# cc2652p_ch340e.net
KiCad netlist of a schematic drawn in EAGLE
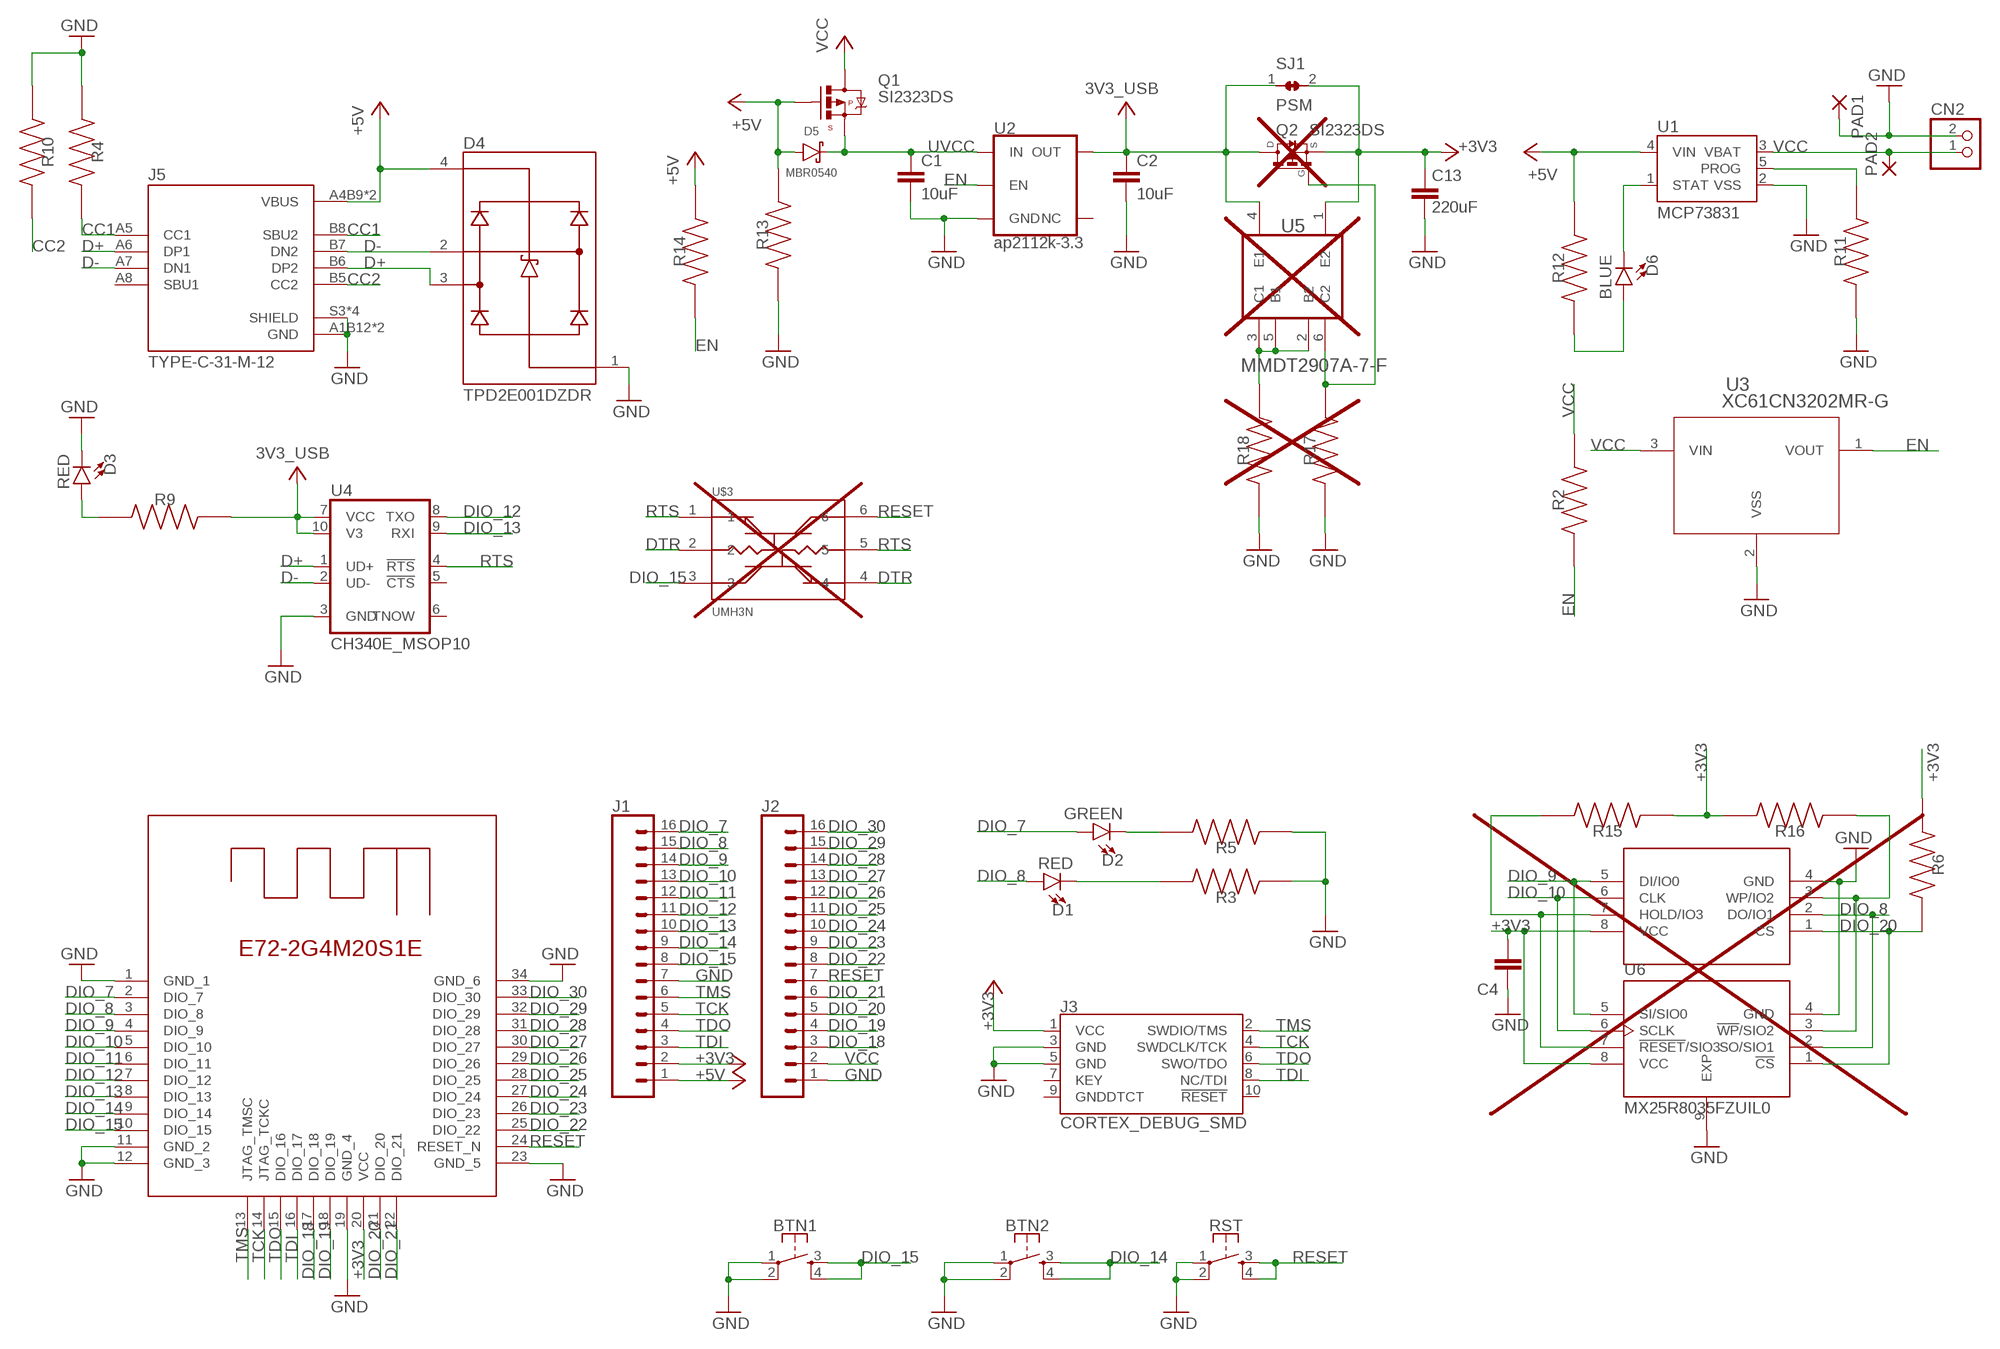
[diagram p0: schematic, sheet 1]

(export (version "E")
  (design (tool "Eeschema 10.0.6"))
  (components
    (comp (ref "BTN1")
      (value "MOMENTARY-SWITCH-SPST-2-SMD-4.6X2.8MM")
      (footprint "eagle-import:TACTILE_SWITCH_SMD_4.6X2.8MM")
      (libsource (lib "eagle-import") (part "MOMENTARY-SWITCH-SPST-2-SMD-4.6X2.8MM"))
    )
    (comp (ref "BTN2")
      (value "MOMENTARY-SWITCH-SPST-2-SMD-4.6X2.8MM")
      (footprint "eagle-import:TACTILE_SWITCH_SMD_4.6X2.8MM")
      (libsource (lib "eagle-import") (part "MOMENTARY-SWITCH-SPST-2-SMD-4.6X2.8MM"))
    )
    (comp (ref "C1")
      (value "10uF")
      (footprint "eagle-import:0603")
      (libsource (lib "eagle-import") (part "10UF-0603-6.3V-20%"))
    )
    (comp (ref "C2")
      (value "10uF")
      (footprint "eagle-import:0603")
      (libsource (lib "eagle-import") (part "10UF-0603-6.3V-20%"))
    )
    (comp (ref "C4")
      (value "100n")
      (footprint "eagle-import:CAPC1005X40N")
      (fields (field (name "MF") "Yageo") (field (name "MP") "RC0402FR-073M6L"))
      (libsource (lib "eagle-import") (part "CAP0402"))
    )
    (comp (ref "C13")
      (value "220uF")
      (footprint "eagle-import:CAPM7343X310")
      (libsource (lib "eagle-import") (part "CTANTALUM-2917(7343-METRIC)_"))
    )
    (comp (ref "CN2")
      (value "JST_2PIN-SMT-RA")
      (footprint "eagle-import:JST-PH-2-SMT-RA")
      (libsource (lib "eagle-import") (part "JST_2PIN-SMT-RA"))
    )
    (comp (ref "D1")
      (value "RED")
      (footprint "eagle-import:LED-0603")
      (libsource (lib "eagle-import") (part "LED-RED0603"))
    )
    (comp (ref "D2")
      (value "GREEN")
      (footprint "eagle-import:LED-0603")
      (libsource (lib "eagle-import") (part "LED-GREEN0603"))
    )
    (comp (ref "D3")
      (value "RED")
      (footprint "eagle-import:LED-0603")
      (libsource (lib "eagle-import") (part "LED-RED0603"))
    )
    (comp (ref "D4")
      (value "TPD2E001DZDR")
      (footprint "eagle-import:SOT192P237X122-4N")
      (fields (field (name "MF") "Texas Instruments"))
      (libsource (lib "eagle-import") (part "TPD2E001DZDR"))
    )
    (comp (ref "D5")
      (value "MBR0540")
      (footprint "eagle-import:SOD-323")
      (libsource (lib "eagle-import") (part "DIODE-SCHOTTKY"))
    )
    (comp (ref "D6")
      (value "BLUE")
      (footprint "eagle-import:LED-0603")
      (libsource (lib "eagle-import") (part "LED-BLUE0603"))
    )
    (comp (ref "J1")
      (value "CONN_161X16_NO_SILK")
      (footprint "eagle-import:1X16_NO_SILK")
      (libsource (lib "eagle-import") (part "CONN_161X16_NO_SILK"))
    )
    (comp (ref "J2")
      (value "CONN_161X16_NO_SILK")
      (footprint "eagle-import:1X16_NO_SILK")
      (libsource (lib "eagle-import") (part "CONN_161X16_NO_SILK"))
    )
    (comp (ref "J3")
      (value "CORTEX_DEBUG_SMD")
      (footprint "eagle-import:SAMTECH_FTSH-105-01")
      (libsource (lib "eagle-import") (part "CORTEX_DEBUG_SMD"))
    )
    (comp (ref "J5")
      (value "TYPE-C-31-M-12")
      (footprint "eagle-import:HRO_TYPE-C-31-M-12")
      (fields (field (name "MF") "HRO Electronics Co., Ltd."))
      (libsource (lib "eagle-import") (part "TYPE-C-31-M-12"))
    )
    (comp (ref "PAD1")
      (value "WIREPADSMD1,27-254")
      (footprint "eagle-import:SMD1,27-2,54")
      (libsource (lib "eagle-import") (part "WIREPADSMD1,27-254"))
    )
    (comp (ref "PAD2")
      (value "WIREPADSMD1,27-254")
      (footprint "eagle-import:SMD1,27-2,54")
      (libsource (lib "eagle-import") (part "WIREPADSMD1,27-254"))
    )
    (comp (ref "Q1")
      (value "SI2323DS")
      (footprint "eagle-import:SOT23")
      (libsource (lib "eagle-import") (part "MOSFET-PCHANNEL"))
    )
    (comp (ref "Q2")
      (value "SI2323DS")
      (footprint "eagle-import:SOT23")
      (fields (field (name "MF") "Vishay Siliconix"))
      (libsource (lib "eagle-import") (part "SI2323DS"))
    )
    (comp (ref "R2")
      (value "10k")
      (footprint "eagle-import:RESC1005X40N")
      (fields (field (name "MF") "Yageo") (field (name "MP") "RC0402FR-073M6L"))
      (libsource (lib "eagle-import") (part "RC0402FR-073M6L"))
    )
    (comp (ref "R3")
      (value "2.2k")
      (footprint "eagle-import:RESC1005X40N")
      (fields (field (name "MF") "Yageo") (field (name "MP") "RC0402FR-073M6L"))
      (libsource (lib "eagle-import") (part "RC0402FR-073M6L"))
    )
    (comp (ref "R4")
      (value "5.1k")
      (footprint "eagle-import:RESC1005X40N")
      (fields (field (name "MF") "Yageo") (field (name "MP") "RC0402FR-073M6L"))
      (libsource (lib "eagle-import") (part "RC0402FR-073M6L"))
    )
    (comp (ref "R5")
      (value "2.2k")
      (footprint "eagle-import:RESC1005X40N")
      (fields (field (name "MF") "Yageo") (field (name "MP") "RC0402FR-073M6L"))
      (libsource (lib "eagle-import") (part "RC0402FR-073M6L"))
    )
    (comp (ref "R6")
      (value "2.2k")
      (footprint "eagle-import:RESC1005X40N")
      (fields (field (name "MF") "Yageo") (field (name "MP") "RC0402FR-073M6L"))
      (libsource (lib "eagle-import") (part "RC0402FR-073M6L"))
    )
    (comp (ref "R9")
      (value "2.2k")
      (footprint "eagle-import:RESC1005X40N")
      (fields (field (name "MF") "Yageo") (field (name "MP") "RC0402FR-073M6L"))
      (libsource (lib "eagle-import") (part "RC0402FR-073M6L"))
    )
    (comp (ref "R10")
      (value "5.1k")
      (footprint "eagle-import:RESC1005X40N")
      (fields (field (name "MF") "Yageo") (field (name "MP") "RC0402FR-073M6L"))
      (libsource (lib "eagle-import") (part "RC0402FR-073M6L"))
    )
    (comp (ref "R11")
      (value "2k")
      (footprint "eagle-import:RESC1005X40N")
      (fields (field (name "MF") "Yageo") (field (name "MP") "RC0402FR-073M6L"))
      (libsource (lib "eagle-import") (part "RC0402FR-073M6L"))
    )
    (comp (ref "R12")
      (value "2.2k")
      (footprint "eagle-import:RESC1005X40N")
      (fields (field (name "MF") "Yageo") (field (name "MP") "RC0402FR-073M6L"))
      (libsource (lib "eagle-import") (part "RC0402FR-073M6L"))
    )
    (comp (ref "R13")
      (value "10k")
      (footprint "eagle-import:RESC1005X40N")
      (fields (field (name "MF") "Yageo") (field (name "MP") "RC0402FR-073M6L"))
      (libsource (lib "eagle-import") (part "RC0402FR-073M6L"))
    )
    (comp (ref "R14")
      (value "10k")
      (footprint "eagle-import:RESC1005X40N")
      (fields (field (name "MF") "Yageo") (field (name "MP") "RC0402FR-073M6L"))
      (libsource (lib "eagle-import") (part "RC0402FR-073M6L"))
    )
    (comp (ref "R15")
      (value "0")
      (footprint "eagle-import:RESC1005X40N")
      (fields (field (name "MF") "Yageo") (field (name "MP") "RC0402FR-073M6L"))
      (libsource (lib "eagle-import") (part "RC0402FR-073M6L"))
    )
    (comp (ref "R16")
      (value "0")
      (footprint "eagle-import:RESC1005X40N")
      (fields (field (name "MF") "Yageo") (field (name "MP") "RC0402FR-073M6L"))
      (libsource (lib "eagle-import") (part "RC0402FR-073M6L"))
    )
    (comp (ref "R17")
      (value "100k")
      (footprint "eagle-import:RESC1005X40N")
      (fields (field (name "MF") "Yageo") (field (name "MP") "RC0402FR-073M6L"))
      (libsource (lib "eagle-import") (part "RC0402FR-073M6L"))
    )
    (comp (ref "R18")
      (value "100k")
      (footprint "eagle-import:RESC1005X40N")
      (fields (field (name "MF") "Yageo") (field (name "MP") "RC0402FR-073M6L"))
      (libsource (lib "eagle-import") (part "RC0402FR-073M6L"))
    )
    (comp (ref "RST")
      (value "MOMENTARY-SWITCH-SPST-2-SMD-4.6X2.8MM")
      (footprint "eagle-import:TACTILE_SWITCH_SMD_4.6X2.8MM")
      (libsource (lib "eagle-import") (part "MOMENTARY-SWITCH-SPST-2-SMD-4.6X2.8MM"))
    )
    (comp (ref "SJ1")
      (value "PSM")
      (footprint "eagle-import:SMALL_SOLDER_JUMPER_CLOSED")
      (libsource (lib "eagle-import") (part "SMALL_SOLDER_JUMPER_CLOSED"))
    )
    (comp (ref "U$1")
      (value "E72-2G4M20S1E")
      (footprint "eagle-import:E72-2G4M20S1E")
      (libsource (lib "eagle-import") (part "E72-2G4M20S1E"))
    )
    (comp (ref "U$2")
      (value "MX25R8035FM1IL0")
      (footprint "eagle-import:SO-8")
      (fields (field (name "MF") "Winbond Electronics") (field (name "MP") "W25Q80BVSNIG"))
      (libsource (lib "eagle-import") (part "W25Q80BVSNIG"))
    )
    (comp (ref "U$3")
      (value "UMH3N")
      (footprint "eagle-import:SOP65P210X100-6N")
      (fields (field (name "MF") "Rohm"))
      (libsource (lib "eagle-import") (part "UMH3N"))
    )
    (comp (ref "U1")
      (value "MCP73831")
      (footprint "eagle-import:SOT23-5")
      (libsource (lib "eagle-import") (part "MCP73831"))
    )
    (comp (ref "U2")
      (value "ap2112k-3.3")
      (footprint "eagle-import:SOT23-5")
      (libsource (lib "eagle-import") (part "V_REG_AP2112K-3.3V"))
    )
    (comp (ref "U3")
      (value "XC61CN3202MR-G")
      (footprint "eagle-import:XC61C_SOT-23_TOR")
      (libsource (lib "eagle-import") (part "XC61CN3202MR-G"))
    )
    (comp (ref "U4")
      (value "CH340E_MSOP10")
      (footprint "eagle-import:MSOP10")
      (fields (field (name "MF") "WCH") (field (name "MP") "CH340E"))
      (libsource (lib "eagle-import") (part "CH340E_MSOP10"))
    )
    (comp (ref "U5")
      (value "MMDT2907A-7-F")
      (footprint "eagle-import:SOT65P210X110-6N")
      (fields (field (name "MF") "Diodes Inc."))
      (libsource (lib "eagle-import") (part "MMDT2907A-7-F"))
    )
    (comp (ref "U6")
      (value "MX25R8035FZUIL0")
      (footprint "eagle-import:PSON50P200X300X60-9N")
      (fields (field (name "MF") "Macronix"))
      (libsource (lib "eagle-import") (part "MX25R8035FZUIL0"))
    )
  )
  (nets
    (net (code "1") (name "+3V3") (class "Default")
      (node (ref "C13") (pin "1") (pinfunction "1_1") (pintype "passive"))
      (node (ref "C4") (pin "2") (pinfunction "2_2") (pintype "passive"))
      (node (ref "J1") (pin "2") (pinfunction "2_2") (pintype "passive"))
      (node (ref "J3") (pin "1") (pinfunction "VCC_1") (pintype "bidirectional"))
      (node (ref "Q2") (pin "2") (pinfunction "S_2") (pintype "passive"))
      (node (ref "R15") (pin "1") (pinfunction "1_1") (pintype "passive"))
      (node (ref "R16") (pin "2") (pinfunction "2_2") (pintype "passive"))
      (node (ref "R6") (pin "1") (pinfunction "1_1") (pintype "passive"))
      (node (ref "SJ1") (pin "2") (pinfunction "2_2") (pintype "bidirectional"))
      (node (ref "U$1") (pin "20") (pinfunction "VCC_20") (pintype "bidirectional"))
      (node (ref "U$2") (pin "8") (pinfunction "VCC_8") (pintype "bidirectional"))
      (node (ref "U5") (pin "1") (pinfunction "E2_1") (pintype "passive"))
      (node (ref "U6") (pin "8") (pinfunction "VCC_8") (pintype "power_in"))
    )
    (net (code "2") (name "+5V") (class "Default")
      (node (ref "D4") (pin "4") (pinfunction "VCC_4") (pintype "power_in"))
      (node (ref "D5") (pin "A") (pinfunction "A_A") (pintype "passive"))
      (node (ref "J1") (pin "1") (pinfunction "1_1") (pintype "passive"))
      (node (ref "J5") (pin "A4B9") (pinfunction "VBUS_A4B9") (pintype "power_in"))
      (node (ref "J5") (pin "B4A9") (pinfunction "VBUS_B4A9") (pintype "power_in"))
      (node (ref "Q1") (pin "1") (pinfunction "G_1") (pintype "passive"))
      (node (ref "R12") (pin "2") (pinfunction "2_2") (pintype "passive"))
      (node (ref "R13") (pin "2") (pinfunction "2_2") (pintype "passive"))
      (node (ref "R14") (pin "2") (pinfunction "2_2") (pintype "passive"))
      (node (ref "U1") (pin "4") (pinfunction "VIN_4") (pintype "power_in"))
    )
    (net (code "3") (name "/CC1") (class "Default")
      (node (ref "J5") (pin "A5") (pinfunction "CC1_A5") (pintype "bidirectional"))
      (node (ref "J5") (pin "B8") (pinfunction "SBU2_B8") (pintype "bidirectional"))
      (node (ref "R4") (pin "2") (pinfunction "2_2") (pintype "passive"))
    )
    (net (code "4") (name "/CC2") (class "Default")
      (node (ref "J5") (pin "B5") (pinfunction "CC2_B5") (pintype "bidirectional"))
      (node (ref "R10") (pin "2") (pinfunction "2_2") (pintype "passive"))
    )
    (net (code "5") (name "/D+") (class "Default")
      (node (ref "D4") (pin "3") (pinfunction "IO2_3") (pintype "bidirectional"))
      (node (ref "J5") (pin "A6") (pinfunction "DP1_A6") (pintype "bidirectional"))
      (node (ref "J5") (pin "B6") (pinfunction "DP2_B6") (pintype "bidirectional"))
      (node (ref "U4") (pin "1") (pinfunction "UD+_1") (pintype "bidirectional"))
    )
    (net (code "6") (name "/D-") (class "Default")
      (node (ref "D4") (pin "2") (pinfunction "IO1_2") (pintype "bidirectional"))
      (node (ref "J5") (pin "A7") (pinfunction "DN1_A7") (pintype "bidirectional"))
      (node (ref "J5") (pin "B7") (pinfunction "DN2_B7") (pintype "bidirectional"))
      (node (ref "U4") (pin "2") (pinfunction "UD-_2") (pintype "bidirectional"))
    )
    (net (code "7") (name "/DIO_7") (class "Default")
      (node (ref "D2") (pin "A") (pinfunction "A_A") (pintype "passive"))
      (node (ref "J1") (pin "16") (pinfunction "16_16") (pintype "passive"))
      (node (ref "U$1") (pin "2") (pinfunction "DIO_7_2") (pintype "bidirectional"))
    )
    (net (code "8") (name "/DIO_8") (class "Default")
      (node (ref "D1") (pin "A") (pinfunction "A_A") (pintype "passive"))
      (node (ref "J1") (pin "15") (pinfunction "15_15") (pintype "passive"))
      (node (ref "U$1") (pin "3") (pinfunction "DIO_8_3") (pintype "bidirectional"))
      (node (ref "U$2") (pin "2") (pinfunction "DO/IO1_2") (pintype "bidirectional"))
      (node (ref "U6") (pin "2") (pinfunction "SO/SIO1_2") (pintype "bidirectional"))
    )
    (net (code "9") (name "/DIO_9") (class "Default")
      (node (ref "J1") (pin "14") (pinfunction "14_14") (pintype "passive"))
      (node (ref "U$1") (pin "4") (pinfunction "DIO_9_4") (pintype "bidirectional"))
      (node (ref "U$2") (pin "5") (pinfunction "DI/IO0_5") (pintype "bidirectional"))
      (node (ref "U6") (pin "5") (pinfunction "SI/SIO0_5") (pintype "bidirectional"))
    )
    (net (code "10") (name "/DIO_10") (class "Default")
      (node (ref "J1") (pin "13") (pinfunction "13_13") (pintype "passive"))
      (node (ref "U$1") (pin "5") (pinfunction "DIO_10_5") (pintype "bidirectional"))
      (node (ref "U$2") (pin "6") (pinfunction "CLK_6") (pintype "bidirectional"))
      (node (ref "U6") (pin "6") (pinfunction "SCLK_6") (pintype "input"))
    )
    (net (code "11") (name "/DIO_11") (class "Default")
      (node (ref "J1") (pin "12") (pinfunction "12_12") (pintype "passive"))
      (node (ref "U$1") (pin "6") (pinfunction "DIO_11_6") (pintype "bidirectional"))
    )
    (net (code "12") (name "/DIO_12") (class "Default")
      (node (ref "J1") (pin "11") (pinfunction "11_11") (pintype "passive"))
      (node (ref "U$1") (pin "7") (pinfunction "DIO_12_7") (pintype "bidirectional"))
      (node (ref "U4") (pin "8") (pinfunction "TXO_8") (pintype "bidirectional"))
    )
    (net (code "13") (name "/DIO_13") (class "Default")
      (node (ref "J1") (pin "10") (pinfunction "10_10") (pintype "passive"))
      (node (ref "U$1") (pin "8") (pinfunction "DIO_13_8") (pintype "bidirectional"))
      (node (ref "U4") (pin "9") (pinfunction "RXI_9") (pintype "bidirectional"))
    )
    (net (code "14") (name "/DIO_14") (class "Default")
      (node (ref "BTN2") (pin "3") (pinfunction "3_3") (pintype "passive"))
      (node (ref "BTN2") (pin "4") (pinfunction "4_4") (pintype "passive"))
      (node (ref "J1") (pin "9") (pinfunction "9_9") (pintype "passive"))
      (node (ref "U$1") (pin "9") (pinfunction "DIO_14_9") (pintype "bidirectional"))
    )
    (net (code "15") (name "/DIO_15") (class "Default")
      (node (ref "BTN1") (pin "3") (pinfunction "3_3") (pintype "passive"))
      (node (ref "BTN1") (pin "4") (pinfunction "4_4") (pintype "passive"))
      (node (ref "J1") (pin "8") (pinfunction "8_8") (pintype "passive"))
      (node (ref "U$1") (pin "10") (pinfunction "DIO_15_10") (pintype "bidirectional"))
      (node (ref "U$3") (pin "3") (pinfunction "3_3") (pintype "bidirectional"))
    )
    (net (code "16") (name "/DIO_18") (class "Default")
      (node (ref "J2") (pin "3") (pinfunction "3_3") (pintype "passive"))
      (node (ref "U$1") (pin "17") (pinfunction "DIO_18_17") (pintype "bidirectional"))
    )
    (net (code "17") (name "/DIO_19") (class "Default")
      (node (ref "J2") (pin "4") (pinfunction "4_4") (pintype "passive"))
      (node (ref "U$1") (pin "18") (pinfunction "DIO_19_18") (pintype "bidirectional"))
    )
    (net (code "18") (name "/DIO_20") (class "Default")
      (node (ref "J2") (pin "5") (pinfunction "5_5") (pintype "passive"))
      (node (ref "R6") (pin "2") (pinfunction "2_2") (pintype "passive"))
      (node (ref "U$1") (pin "21") (pinfunction "DIO_20_21") (pintype "bidirectional"))
      (node (ref "U$2") (pin "1") (pinfunction "CS_1") (pintype "bidirectional"))
      (node (ref "U6") (pin "1") (pinfunction "~{CS}_1") (pintype "input"))
    )
    (net (code "19") (name "/DIO_21") (class "Default")
      (node (ref "J2") (pin "6") (pinfunction "6_6") (pintype "passive"))
      (node (ref "U$1") (pin "22") (pinfunction "DIO_21_22") (pintype "bidirectional"))
    )
    (net (code "20") (name "/DIO_22") (class "Default")
      (node (ref "J2") (pin "8") (pinfunction "8_8") (pintype "passive"))
      (node (ref "U$1") (pin "25") (pinfunction "DIO_22_25") (pintype "bidirectional"))
    )
    (net (code "21") (name "/DIO_23") (class "Default")
      (node (ref "J2") (pin "9") (pinfunction "9_9") (pintype "passive"))
      (node (ref "U$1") (pin "26") (pinfunction "DIO_23_26") (pintype "bidirectional"))
    )
    (net (code "22") (name "/DIO_24") (class "Default")
      (node (ref "J2") (pin "10") (pinfunction "10_10") (pintype "passive"))
      (node (ref "U$1") (pin "27") (pinfunction "DIO_24_27") (pintype "bidirectional"))
    )
    (net (code "23") (name "/DIO_25") (class "Default")
      (node (ref "J2") (pin "11") (pinfunction "11_11") (pintype "passive"))
      (node (ref "U$1") (pin "28") (pinfunction "DIO_25_28") (pintype "bidirectional"))
    )
    (net (code "24") (name "/DIO_26") (class "Default")
      (node (ref "J2") (pin "12") (pinfunction "12_12") (pintype "passive"))
      (node (ref "U$1") (pin "29") (pinfunction "DIO_26_29") (pintype "bidirectional"))
    )
    (net (code "25") (name "/DIO_27") (class "Default")
      (node (ref "J2") (pin "13") (pinfunction "13_13") (pintype "passive"))
      (node (ref "U$1") (pin "30") (pinfunction "DIO_27_30") (pintype "bidirectional"))
    )
    (net (code "26") (name "/DIO_28") (class "Default")
      (node (ref "J2") (pin "14") (pinfunction "14_14") (pintype "passive"))
      (node (ref "U$1") (pin "31") (pinfunction "DIO_28_31") (pintype "bidirectional"))
    )
    (net (code "27") (name "/DIO_29") (class "Default")
      (node (ref "J2") (pin "15") (pinfunction "15_15") (pintype "passive"))
      (node (ref "U$1") (pin "32") (pinfunction "DIO_29_32") (pintype "bidirectional"))
    )
    (net (code "28") (name "/DIO_30") (class "Default")
      (node (ref "J2") (pin "16") (pinfunction "16_16") (pintype "passive"))
      (node (ref "U$1") (pin "33") (pinfunction "DIO_30_33") (pintype "bidirectional"))
    )
    (net (code "29") (name "/DTR") (class "Default")
      (node (ref "U$3") (pin "2") (pinfunction "2_2") (pintype "bidirectional"))
      (node (ref "U$3") (pin "4") (pinfunction "4_4") (pintype "bidirectional"))
    )
    (net (code "30") (name "/EN") (class "Default")
      (node (ref "R14") (pin "1") (pinfunction "1_1") (pintype "passive"))
      (node (ref "R2") (pin "1") (pinfunction "1_1") (pintype "passive"))
      (node (ref "U2") (pin "3") (pinfunction "EN_3") (pintype "input"))
      (node (ref "U3") (pin "1") (pinfunction "VOUT_1") (pintype "output"))
    )
    (net (code "31") (name "/RESET") (class "Default")
      (node (ref "J2") (pin "7") (pinfunction "7_7") (pintype "passive"))
      (node (ref "RST") (pin "3") (pinfunction "3_3") (pintype "passive"))
      (node (ref "RST") (pin "4") (pinfunction "4_4") (pintype "passive"))
      (node (ref "U$1") (pin "24") (pinfunction "RESET_N_24") (pintype "bidirectional"))
      (node (ref "U$3") (pin "6") (pinfunction "6_6") (pintype "bidirectional"))
    )
    (net (code "32") (name "/RTS") (class "Default")
      (node (ref "U$3") (pin "1") (pinfunction "1_1") (pintype "bidirectional"))
      (node (ref "U$3") (pin "5") (pinfunction "5_5") (pintype "bidirectional"))
      (node (ref "U4") (pin "4") (pinfunction "~{RTS}_4") (pintype "bidirectional"))
    )
    (net (code "33") (name "/TCK") (class "Default")
      (node (ref "J1") (pin "5") (pinfunction "5_5") (pintype "passive"))
      (node (ref "J3") (pin "4") (pinfunction "SWDCLK/TCK_4") (pintype "bidirectional"))
      (node (ref "U$1") (pin "14") (pinfunction "JTAG_TCKC_14") (pintype "bidirectional"))
    )
    (net (code "34") (name "/TDI") (class "Default")
      (node (ref "J1") (pin "3") (pinfunction "3_3") (pintype "passive"))
      (node (ref "J3") (pin "8") (pinfunction "NC/TDI_8") (pintype "bidirectional"))
      (node (ref "U$1") (pin "16") (pinfunction "DIO_17_16") (pintype "bidirectional"))
    )
    (net (code "35") (name "/TDO") (class "Default")
      (node (ref "J1") (pin "4") (pinfunction "4_4") (pintype "passive"))
      (node (ref "J3") (pin "6") (pinfunction "SWO/TDO_6") (pintype "bidirectional"))
      (node (ref "U$1") (pin "15") (pinfunction "DIO_16_15") (pintype "bidirectional"))
    )
    (net (code "36") (name "/TMS") (class "Default")
      (node (ref "J1") (pin "6") (pinfunction "6_6") (pintype "passive"))
      (node (ref "J3") (pin "2") (pinfunction "SWDIO/TMS_2") (pintype "bidirectional"))
      (node (ref "U$1") (pin "13") (pinfunction "JTAG_TMSC_13") (pintype "bidirectional"))
    )
    (net (code "37") (name "/UVCC") (class "Default")
      (node (ref "C1") (pin "1") (pinfunction "1_1") (pintype "passive"))
      (node (ref "D5") (pin "C") (pinfunction "C_C") (pintype "passive"))
      (node (ref "Q1") (pin "2") (pinfunction "S_2") (pintype "passive"))
      (node (ref "U2") (pin "1") (pinfunction "IN_1") (pintype "input"))
    )
    (net (code "38") (name "3V3_USB") (class "Default")
      (node (ref "C2") (pin "1") (pinfunction "1_1") (pintype "passive"))
      (node (ref "Q2") (pin "3") (pinfunction "D_3") (pintype "passive"))
      (node (ref "R9") (pin "1") (pinfunction "1_1") (pintype "passive"))
      (node (ref "SJ1") (pin "1") (pinfunction "1_1") (pintype "bidirectional"))
      (node (ref "U2") (pin "5") (pinfunction "OUT_5") (pintype "passive"))
      (node (ref "U4") (pin "10") (pinfunction "V3_10") (pintype "bidirectional"))
      (node (ref "U4") (pin "7") (pinfunction "VCC_7") (pintype "bidirectional"))
      (node (ref "U5") (pin "4") (pinfunction "E1_4") (pintype "passive"))
    )
    (net (code "39") (name "GND") (class "Default")
      (node (ref "BTN1") (pin "1") (pinfunction "1_1") (pintype "passive"))
      (node (ref "BTN1") (pin "2") (pinfunction "2_2") (pintype "passive"))
      (node (ref "BTN2") (pin "1") (pinfunction "1_1") (pintype "passive"))
      (node (ref "BTN2") (pin "2") (pinfunction "2_2") (pintype "passive"))
      (node (ref "C1") (pin "2") (pinfunction "2_2") (pintype "passive"))
      (node (ref "C13") (pin "2") (pinfunction "2_2") (pintype "passive"))
      (node (ref "C2") (pin "2") (pinfunction "2_2") (pintype "passive"))
      (node (ref "C4") (pin "1") (pinfunction "1_1") (pintype "passive"))
      (node (ref "CN2") (pin "2") (pinfunction "1_2") (pintype "passive"))
      (node (ref "D3") (pin "C") (pinfunction "C_C") (pintype "passive"))
      (node (ref "D4") (pin "1") (pinfunction "GND_1") (pintype "power_in"))
      (node (ref "J1") (pin "7") (pinfunction "7_7") (pintype "passive"))
      (node (ref "J2") (pin "1") (pinfunction "1_1") (pintype "passive"))
      (node (ref "J3") (pin "3") (pinfunction "GND_3") (pintype "bidirectional"))
      (node (ref "J3") (pin "5") (pinfunction "GND_5") (pintype "bidirectional"))
      (node (ref "J5") (pin "A1B12") (pinfunction "GND_A1B12") (pintype "power_in"))
      (node (ref "J5") (pin "B1A12") (pinfunction "GND_B1A12") (pintype "power_in"))
      (node (ref "J5") (pin "S3") (pinfunction "SHIELD_S3") (pintype "passive"))
      (node (ref "J5") (pin "S4") (pinfunction "SHIELD_S4") (pintype "passive"))
      (node (ref "J5") (pin "S5") (pinfunction "SHIELD_S5") (pintype "passive"))
      (node (ref "J5") (pin "S6") (pinfunction "SHIELD_S6") (pintype "passive"))
      (node (ref "PAD1") (pin "1") (pinfunction "P_1") (pintype "passive"))
      (node (ref "R10") (pin "1") (pinfunction "1_1") (pintype "passive"))
      (node (ref "R11") (pin "1") (pinfunction "1_1") (pintype "passive"))
      (node (ref "R13") (pin "1") (pinfunction "1_1") (pintype "passive"))
      (node (ref "R17") (pin "1") (pinfunction "1_1") (pintype "passive"))
      (node (ref "R18") (pin "1") (pinfunction "1_1") (pintype "passive"))
      (node (ref "R3") (pin "1") (pinfunction "1_1") (pintype "passive"))
      (node (ref "R4") (pin "1") (pinfunction "1_1") (pintype "passive"))
      (node (ref "R5") (pin "1") (pinfunction "1_1") (pintype "passive"))
      (node (ref "RST") (pin "1") (pinfunction "1_1") (pintype "passive"))
      (node (ref "RST") (pin "2") (pinfunction "2_2") (pintype "passive"))
      (node (ref "U$1") (pin "1") (pinfunction "GND_1_1") (pintype "bidirectional"))
      (node (ref "U$1") (pin "11") (pinfunction "GND_2_11") (pintype "bidirectional"))
      (node (ref "U$1") (pin "12") (pinfunction "GND_3_12") (pintype "bidirectional"))
      (node (ref "U$1") (pin "19") (pinfunction "GND_4_19") (pintype "bidirectional"))
      (node (ref "U$1") (pin "23") (pinfunction "GND_5_23") (pintype "bidirectional"))
      (node (ref "U$1") (pin "34") (pinfunction "GND_6_34") (pintype "bidirectional"))
      (node (ref "U$2") (pin "4") (pinfunction "GND_4") (pintype "bidirectional"))
      (node (ref "U1") (pin "2") (pinfunction "VSS_2") (pintype "power_in"))
      (node (ref "U2") (pin "2") (pinfunction "GND_2") (pintype "input"))
      (node (ref "U3") (pin "2") (pinfunction "VSS_2") (pintype "passive"))
      (node (ref "U4") (pin "3") (pinfunction "GND_3") (pintype "bidirectional"))
      (node (ref "U6") (pin "4") (pinfunction "GND_4") (pintype "power_in"))
      (node (ref "U6") (pin "9") (pinfunction "EXP_9") (pintype "power_in"))
    )
    (net (code "40") (name "Net-(D1-PadC)") (class "Default")
      (node (ref "D1") (pin "C") (pinfunction "C_C") (pintype "passive"))
      (node (ref "R3") (pin "2") (pinfunction "2_2") (pintype "passive"))
    )
    (net (code "41") (name "Net-(D2-PadC)") (class "Default")
      (node (ref "D2") (pin "C") (pinfunction "C_C") (pintype "passive"))
      (node (ref "R5") (pin "2") (pinfunction "2_2") (pintype "passive"))
    )
    (net (code "42") (name "Net-(D3-PadA)") (class "Default")
      (node (ref "D3") (pin "A") (pinfunction "A_A") (pintype "passive"))
      (node (ref "R9") (pin "2") (pinfunction "2_2") (pintype "passive"))
    )
    (net (code "43") (name "Net-(D6-PadA)") (class "Default")
      (node (ref "D6") (pin "A") (pinfunction "A_A") (pintype "passive"))
      (node (ref "R12") (pin "1") (pinfunction "1_1") (pintype "passive"))
    )
    (net (code "44") (name "Net-(Q2-G)") (class "Default")
      (node (ref "Q2") (pin "1") (pinfunction "G_1") (pintype "passive"))
      (node (ref "R17") (pin "2") (pinfunction "2_2") (pintype "passive"))
      (node (ref "U5") (pin "6") (pinfunction "C2_6") (pintype "passive"))
    )
    (net (code "45") (name "Net-(U$2-HOLD{slash}IO3)") (class "Default")
      (node (ref "R15") (pin "2") (pinfunction "2_2") (pintype "passive"))
      (node (ref "U$2") (pin "7") (pinfunction "HOLD/IO3_7") (pintype "bidirectional"))
      (node (ref "U6") (pin "7") (pinfunction "~{RESET}/SIO3_7") (pintype "bidirectional"))
    )
    (net (code "46") (name "Net-(U$2-WP{slash}IO2)") (class "Default")
      (node (ref "R16") (pin "1") (pinfunction "1_1") (pintype "passive"))
      (node (ref "U$2") (pin "3") (pinfunction "WP/IO2_3") (pintype "bidirectional"))
      (node (ref "U6") (pin "3") (pinfunction "~{WP}/SIO2_3") (pintype "bidirectional"))
    )
    (net (code "47") (name "Net-(U1-PROG)") (class "Default")
      (node (ref "R11") (pin "2") (pinfunction "2_2") (pintype "passive"))
      (node (ref "U1") (pin "5") (pinfunction "PROG_5") (pintype "input"))
    )
    (net (code "48") (name "Net-(U1-STAT)") (class "Default")
      (node (ref "D6") (pin "C") (pinfunction "C_C") (pintype "passive"))
      (node (ref "U1") (pin "1") (pinfunction "STAT_1") (pintype "output"))
    )
    (net (code "49") (name "Net-(U5-B1)") (class "Default")
      (node (ref "R18") (pin "2") (pinfunction "2_2") (pintype "passive"))
      (node (ref "U5") (pin "2") (pinfunction "B2_2") (pintype "passive"))
      (node (ref "U5") (pin "3") (pinfunction "C1_3") (pintype "passive"))
      (node (ref "U5") (pin "5") (pinfunction "B1_5") (pintype "passive"))
    )
    (net (code "50") (name "VCC") (class "Default")
      (node (ref "CN2") (pin "1") (pinfunction "2_1") (pintype "passive"))
      (node (ref "J2") (pin "2") (pinfunction "2_2") (pintype "passive"))
      (node (ref "PAD2") (pin "1") (pinfunction "P_1") (pintype "passive"))
      (node (ref "Q1") (pin "3") (pinfunction "D_3") (pintype "passive"))
      (node (ref "R2") (pin "2") (pinfunction "2_2") (pintype "passive"))
      (node (ref "U1") (pin "3") (pinfunction "VBAT_3") (pintype "power_in"))
      (node (ref "U3") (pin "3") (pinfunction "VIN_3") (pintype "power_in"))
    )
    (net (code "51") (name "unconnected-(J3-GNDDTCT-Pad9)") (class "Default")
      (node (ref "J3") (pin "9") (pinfunction "GNDDTCT_9") (pintype "bidirectional"))
    )
    (net (code "52") (name "unconnected-(J3-KEY-Pad7)") (class "Default")
      (node (ref "J3") (pin "7") (pinfunction "KEY_7") (pintype "bidirectional"))
    )
    (net (code "53") (name "unconnected-(J3-~{RESET}-Pad10)") (class "Default")
      (node (ref "J3") (pin "10") (pinfunction "~{RESET}_10") (pintype "bidirectional"))
    )
    (net (code "54") (name "unconnected-(J5-SBU1-PadA8)") (class "Default")
      (node (ref "J5") (pin "A8") (pinfunction "SBU1_A8") (pintype "bidirectional"))
    )
    (net (code "55") (name "unconnected-(U2-NC-Pad4)") (class "Default")
      (node (ref "U2") (pin "4") (pinfunction "NC_4") (pintype "no_connect"))
    )
    (net (code "56") (name "unconnected-(U4-TNOW-Pad6)") (class "Default")
      (node (ref "U4") (pin "6") (pinfunction "TNOW_6") (pintype "bidirectional"))
    )
    (net (code "57") (name "unconnected-(U4-~{CTS}-Pad5)") (class "Default")
      (node (ref "U4") (pin "5") (pinfunction "~{CTS}_5") (pintype "bidirectional"))
    )
  )
)
